# plugV17-Add-Large-Cap-to-support-RELAY-s.net
KiCad netlist of a schematic drawn in EAGLE
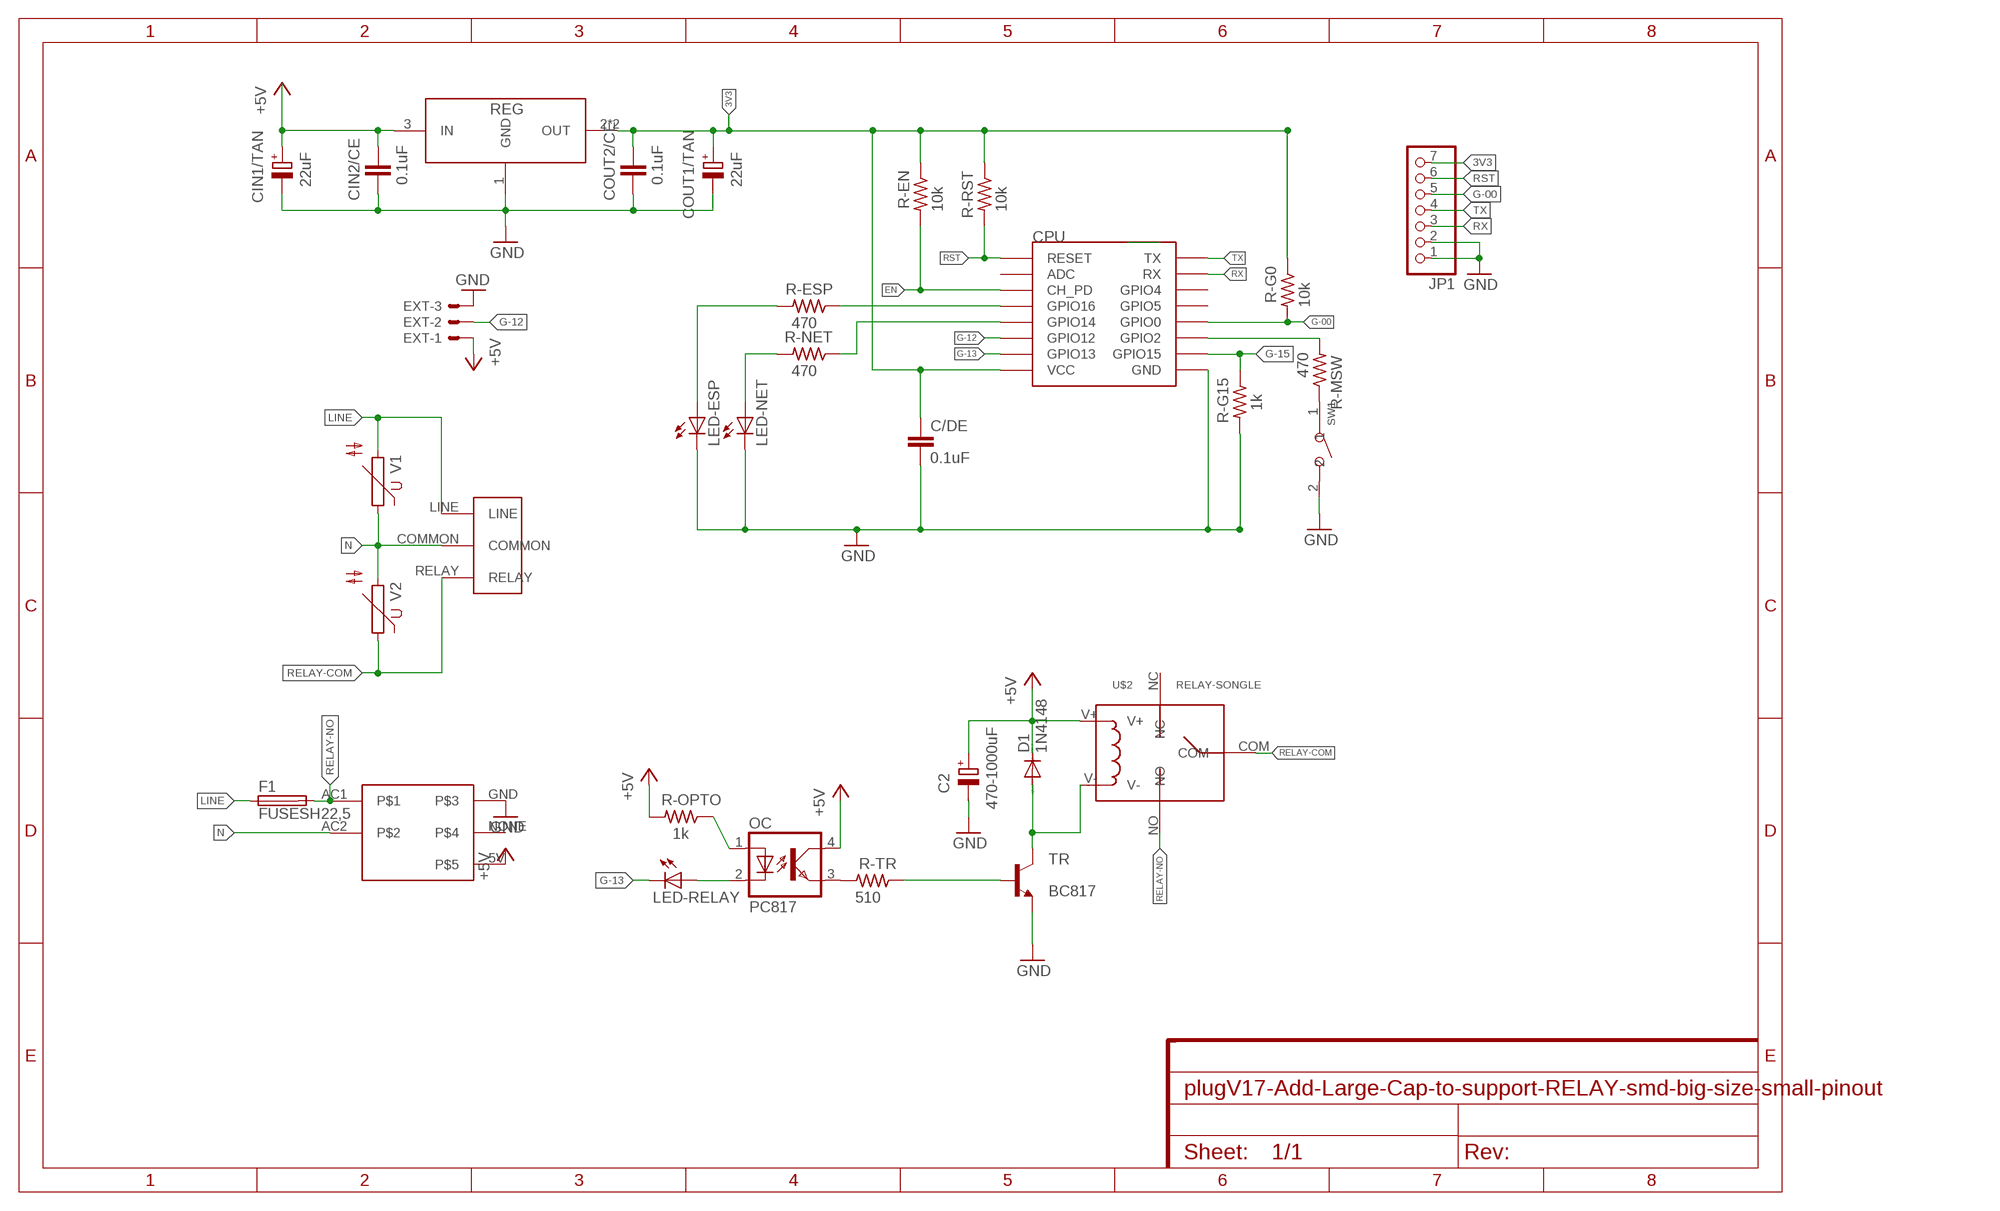
[diagram p0: schematic, sheet 1]

(export (version "E")
  (design (tool "Eeschema 10.0.6"))
  (components
    (comp (ref "C/DE")
      (value "0.1uF")
      (footprint "eagle-import:C0805")
      (libsource (lib "eagle-import") (part "C-EUC0805"))
    )
    (comp (ref "C2")
      (value "470-1000uF")
      (footprint "eagle-import:E3,5-8")
      (libsource (lib "eagle-import") (part "CPOL-EUE3.5-8"))
    )
    (comp (ref "CIN1/TAN")
      (value "22uF")
      (footprint "eagle-import:B_3528-21R")
      (libsource (lib "eagle-import") (part "CPOL-EUB/3528-21R"))
    )
    (comp (ref "CIN2/CE")
      (value "0.1uF")
      (footprint "eagle-import:C0805K")
      (libsource (lib "eagle-import") (part "C-EUC0805K"))
    )
    (comp (ref "COUT1/TAN")
      (value "22uF")
      (footprint "eagle-import:B_3528-21R")
      (libsource (lib "eagle-import") (part "CPOL-EUB/3528-21R"))
    )
    (comp (ref "COUT2/CE")
      (value "0.1uF")
      (footprint "eagle-import:C0805K")
      (libsource (lib "eagle-import") (part "C-EUC0805K"))
    )
    (comp (ref "CPU")
      (value "ESP12SMD")
      (footprint "eagle-import:ESP12-SMD")
      (libsource (lib "eagle-import") (part "ESP12SMD"))
    )
    (comp (ref "D1")
      (value "1N4148")
      (footprint "eagle-import:DO35-7")
      (libsource (lib "eagle-import") (part "1N4148DO35-7"))
    )
    (comp (ref "EXT")
      (value "53048-03")
      (footprint "eagle-import:53048-03")
      (fields (field (name "MF") "WALDOM/MOLEX") (field (name "MPN") "53048-0310"))
      (libsource (lib "eagle-import") (part "53?-03048"))
    )
    (comp (ref "F1")
      (value "FUSESH22,5")
      (footprint "eagle-import:SH22,5")
      (libsource (lib "eagle-import") (part "FUSESH22,5"))
    )
    (comp (ref "JP1")
      (value "PINHD-1X7")
      (footprint "eagle-import:1X07")
      (libsource (lib "eagle-import") (part "PINHD-1X7"))
    )
    (comp (ref "LED-ESP")
      (value "LEDCHIPLED_0805")
      (footprint "eagle-import:CHIPLED_0805")
      (libsource (lib "eagle-import") (part "LEDCHIPLED_0805"))
    )
    (comp (ref "LED-NET")
      (value "LEDCHIPLED_0805")
      (footprint "eagle-import:CHIPLED_0805")
      (libsource (lib "eagle-import") (part "LEDCHIPLED_0805"))
    )
    (comp (ref "LED-RELAY")
      (value "LEDCHIPLED_0805")
      (footprint "eagle-import:CHIPLED_0805")
      (libsource (lib "eagle-import") (part "LEDCHIPLED_0805"))
    )
    (comp (ref "OC")
      (value "PC817")
      (footprint "eagle-import:DIL04")
      (fields (field (name "MPN") "PC817X4J000F"))
      (libsource (lib "eagle-import") (part "PC817"))
    )
    (comp (ref "R-EN")
      (value "10k")
      (footprint "eagle-import:M0805")
      (libsource (lib "eagle-import") (part "R-US_M0805"))
    )
    (comp (ref "R-ESP")
      (value "470")
      (footprint "eagle-import:M0805")
      (libsource (lib "eagle-import") (part "R-US_M0805"))
    )
    (comp (ref "R-G0")
      (value "10k")
      (footprint "eagle-import:M0805")
      (libsource (lib "eagle-import") (part "R-US_M0805"))
    )
    (comp (ref "R-G15")
      (value "1k")
      (footprint "eagle-import:M0805")
      (libsource (lib "eagle-import") (part "R-US_M0805"))
    )
    (comp (ref "R-MSW")
      (value "470")
      (footprint "eagle-import:M0805")
      (libsource (lib "eagle-import") (part "R-US_M0805"))
    )
    (comp (ref "R-NET")
      (value "470")
      (footprint "eagle-import:M0805")
      (libsource (lib "eagle-import") (part "R-US_M0805"))
    )
    (comp (ref "R-OPTO")
      (value "1k")
      (footprint "eagle-import:M0805")
      (libsource (lib "eagle-import") (part "R-US_M0805"))
    )
    (comp (ref "R-RST")
      (value "10k")
      (footprint "eagle-import:M0805")
      (libsource (lib "eagle-import") (part "R-US_M0805"))
    )
    (comp (ref "R-TR")
      (value "510")
      (footprint "eagle-import:M0805")
      (libsource (lib "eagle-import") (part "R-US_M0805"))
    )
    (comp (ref "REG")
      (value "AMS1117-3.3")
      (footprint "eagle-import:SOT-223")
      (libsource (lib "eagle-import") (part "AMS1117-3.3"))
    )
    (comp (ref "SW1")
      (value "DIP-BUTTON(2P-6.0X3.0X4.3MM)-TS-1101F")
      (footprint "eagle-import:SW2-5.0-6.0X3.0X4.3MM")
      (libsource (lib "eagle-import") (part "DIP-BUTTON(2P-6.0X3.0X4.3MM)-TS-1101F"))
    )
    (comp (ref "TR")
      (value "BC817")
      (footprint "eagle-import:SOT23-BEC")
      (libsource (lib "eagle-import") (part "BC817SMD-16"))
    )
    (comp (ref "U$1")
      (value "POWER-RELAY-FOOTPRINT")
      (footprint "eagle-import:POWER-RELAY-FOOTPRINT")
      (libsource (lib "eagle-import") (part "POWER-RELAY-FOOTPRINT"))
    )
    (comp (ref "U$2")
      (value "RELAY-SONGLE")
      (footprint "eagle-import:RELAY-SONGLE")
      (libsource (lib "eagle-import") (part "RELAY-SONGLE"))
    )
    (comp (ref "U$4")
      (value "POWERSUPPLY-5V-700MA")
      (footprint "eagle-import:POWERSUPPLY-5V-700MA")
      (libsource (lib "eagle-import") (part "POWERSUPPLY-5V-700MA"))
    )
    (comp (ref "V1")
      (value "S14K11")
      (footprint "eagle-import:S14K11")
      (libsource (lib "eagle-import") (part "S14K11"))
    )
    (comp (ref "V2")
      (value "S14K11")
      (footprint "eagle-import:S14K11")
      (libsource (lib "eagle-import") (part "S14K11"))
    )
  )
  (nets
    (net (code "1") (name "+5V") (class "Default")
      (node (ref "C2") (pin "+") (pinfunction "+_+") (pintype "passive"))
      (node (ref "CIN1/TAN") (pin "+") (pinfunction "+_+") (pintype "passive"))
      (node (ref "CIN2/CE") (pin "1") (pinfunction "1_1") (pintype "passive"))
      (node (ref "D1") (pin "C") (pinfunction "C_C") (pintype "passive"))
      (node (ref "EXT") (pin "1") (pinfunction "S_1") (pintype "passive"))
      (node (ref "OC") (pin "4") (pinfunction "COL_4") (pintype "passive"))
      (node (ref "R-OPTO") (pin "2") (pinfunction "2_2") (pintype "passive"))
      (node (ref "REG") (pin "3") (pinfunction "IN_3") (pintype "input"))
      (node (ref "U$2") (pin "V+") (pinfunction "V+_V+") (pintype "bidirectional"))
      (node (ref "U$4") (pin "5V") (pinfunction "P$5_5V") (pintype "bidirectional"))
    )
    (net (code "2") (name "3V3") (class "Default")
      (node (ref "C/DE") (pin "1") (pinfunction "1_1") (pintype "passive"))
      (node (ref "COUT1/TAN") (pin "+") (pinfunction "+_+") (pintype "passive"))
      (node (ref "COUT2/CE") (pin "1") (pinfunction "1_1") (pintype "passive"))
      (node (ref "CPU") (pin "VCC") (pinfunction "VCC_VCC") (pintype "bidirectional"))
      (node (ref "JP1") (pin "7") (pinfunction "7_7") (pintype "passive"))
      (node (ref "R-EN") (pin "1") (pinfunction "1_1") (pintype "passive"))
      (node (ref "R-G0") (pin "1") (pinfunction "1_1") (pintype "passive"))
      (node (ref "R-RST") (pin "1") (pinfunction "1_1") (pintype "passive"))
      (node (ref "REG") (pin "2") (pinfunction "OUT_2") (pintype "output"))
      (node (ref "REG") (pin "4") (pinfunction "OUT_4") (pintype "output"))
    )
    (net (code "3") (name "EN") (class "Default")
      (node (ref "CPU") (pin "CH_PD") (pinfunction "CH_PD_CH_PD") (pintype "bidirectional"))
      (node (ref "R-EN") (pin "2") (pinfunction "2_2") (pintype "passive"))
    )
    (net (code "4") (name "G-00") (class "Default")
      (node (ref "CPU") (pin "GPIO0") (pinfunction "GPIO0_GPIO0") (pintype "bidirectional"))
      (node (ref "JP1") (pin "5") (pinfunction "5_5") (pintype "passive"))
      (node (ref "R-G0") (pin "2") (pinfunction "2_2") (pintype "passive"))
    )
    (net (code "5") (name "G-12") (class "Default")
      (node (ref "CPU") (pin "GPIO12") (pinfunction "GPIO12_GPIO12") (pintype "bidirectional"))
      (node (ref "EXT") (pin "2") (pinfunction "S_2") (pintype "passive"))
    )
    (net (code "6") (name "G-13") (class "Default")
      (node (ref "CPU") (pin "GPIO13") (pinfunction "GPIO13_GPIO13") (pintype "bidirectional"))
      (node (ref "LED-RELAY") (pin "C") (pinfunction "C_C") (pintype "passive"))
    )
    (net (code "7") (name "G-15") (class "Default")
      (node (ref "CPU") (pin "GPIO15") (pinfunction "GPIO15_GPIO15") (pintype "bidirectional"))
      (node (ref "R-G15") (pin "1") (pinfunction "1_1") (pintype "passive"))
    )
    (net (code "8") (name "GND") (class "Default")
      (node (ref "C/DE") (pin "2") (pinfunction "2_2") (pintype "passive"))
      (node (ref "C2") (pin "-") (pinfunction "-_-") (pintype "passive"))
      (node (ref "CIN1/TAN") (pin "-") (pinfunction "-_-") (pintype "passive"))
      (node (ref "CIN2/CE") (pin "2") (pinfunction "2_2") (pintype "passive"))
      (node (ref "COUT1/TAN") (pin "-") (pinfunction "-_-") (pintype "passive"))
      (node (ref "COUT2/CE") (pin "2") (pinfunction "2_2") (pintype "passive"))
      (node (ref "CPU") (pin "GND") (pinfunction "GND_GND") (pintype "bidirectional"))
      (node (ref "EXT") (pin "3") (pinfunction "S_3") (pintype "passive"))
      (node (ref "JP1") (pin "1") (pinfunction "1_1") (pintype "passive"))
      (node (ref "JP1") (pin "2") (pinfunction "2_2") (pintype "passive"))
      (node (ref "LED-ESP") (pin "C") (pinfunction "C_C") (pintype "passive"))
      (node (ref "LED-NET") (pin "C") (pinfunction "C_C") (pintype "passive"))
      (node (ref "R-G15") (pin "2") (pinfunction "2_2") (pintype "passive"))
      (node (ref "REG") (pin "1") (pinfunction "GND_1") (pintype "passive"))
      (node (ref "SW1") (pin "2") (pinfunction "2_2") (pintype "bidirectional"))
      (node (ref "TR") (pin "E") (pinfunction "E_E") (pintype "passive"))
      (node (ref "U$4") (pin "GND") (pinfunction "P$3_GND") (pintype "bidirectional"))
    )
    (net (code "9") (name "LINE") (class "Default")
      (node (ref "F1") (pin "1") (pinfunction "1_1") (pintype "passive"))
      (node (ref "U$1") (pin "LINE") (pinfunction "LINE_LINE") (pintype "bidirectional"))
      (node (ref "V1") (pin "2") (pinfunction "2_2") (pintype "passive"))
    )
    (net (code "10") (name "N") (class "Default")
      (node (ref "U$1") (pin "COMMON") (pinfunction "COMMON_COMMON") (pintype "bidirectional"))
      (node (ref "U$4") (pin "AC2") (pinfunction "P$2_AC2") (pintype "bidirectional"))
      (node (ref "V1") (pin "1") (pinfunction "1_1") (pintype "passive"))
      (node (ref "V2") (pin "2") (pinfunction "2_2") (pintype "passive"))
    )
    (net (code "11") (name "Net-(CPU-PadGPIO2)") (class "Default")
      (node (ref "CPU") (pin "GPIO2") (pinfunction "GPIO2_GPIO2") (pintype "bidirectional"))
      (node (ref "R-MSW") (pin "2") (pinfunction "2_2") (pintype "passive"))
    )
    (net (code "12") (name "Net-(CPU-PadGPIO14)") (class "Default")
      (node (ref "CPU") (pin "GPIO14") (pinfunction "GPIO14_GPIO14") (pintype "bidirectional"))
      (node (ref "R-NET") (pin "1") (pinfunction "1_1") (pintype "passive"))
    )
    (net (code "13") (name "Net-(CPU-PadGPIO16)") (class "Default")
      (node (ref "CPU") (pin "GPIO16") (pinfunction "GPIO16_GPIO16") (pintype "bidirectional"))
      (node (ref "R-ESP") (pin "1") (pinfunction "1_1") (pintype "passive"))
    )
    (net (code "14") (name "Net-(D1-PadA)") (class "Default")
      (node (ref "D1") (pin "A") (pinfunction "A_A") (pintype "passive"))
      (node (ref "TR") (pin "C") (pinfunction "C_C") (pintype "passive"))
      (node (ref "U$2") (pin "V-") (pinfunction "V-_V-") (pintype "bidirectional"))
    )
    (net (code "15") (name "Net-(LED-ESP-PadA)") (class "Default")
      (node (ref "LED-ESP") (pin "A") (pinfunction "A_A") (pintype "passive"))
      (node (ref "R-ESP") (pin "2") (pinfunction "2_2") (pintype "passive"))
    )
    (net (code "16") (name "Net-(LED-NET-PadA)") (class "Default")
      (node (ref "LED-NET") (pin "A") (pinfunction "A_A") (pintype "passive"))
      (node (ref "R-NET") (pin "2") (pinfunction "2_2") (pintype "passive"))
    )
    (net (code "17") (name "Net-(OC-A)") (class "Default")
      (node (ref "OC") (pin "1") (pinfunction "A_1") (pintype "passive"))
      (node (ref "R-OPTO") (pin "1") (pinfunction "1_1") (pintype "passive"))
    )
    (net (code "18") (name "Net-(OC-C)") (class "Default")
      (node (ref "LED-RELAY") (pin "A") (pinfunction "A_A") (pintype "passive"))
      (node (ref "OC") (pin "2") (pinfunction "C_2") (pintype "passive"))
    )
    (net (code "19") (name "Net-(OC-EMIT)") (class "Default")
      (node (ref "OC") (pin "3") (pinfunction "EMIT_3") (pintype "passive"))
      (node (ref "R-TR") (pin "2") (pinfunction "2_2") (pintype "passive"))
    )
    (net (code "20") (name "Net-(R-MSW-Pad1)") (class "Default")
      (node (ref "R-MSW") (pin "1") (pinfunction "1_1") (pintype "passive"))
      (node (ref "SW1") (pin "1") (pinfunction "1_1") (pintype "bidirectional"))
    )
    (net (code "21") (name "Net-(R-TR-Pad1)") (class "Default")
      (node (ref "R-TR") (pin "1") (pinfunction "1_1") (pintype "passive"))
      (node (ref "TR") (pin "B") (pinfunction "B_B") (pintype "passive"))
    )
    (net (code "22") (name "RELAY-COM") (class "Default")
      (node (ref "U$1") (pin "RELAY") (pinfunction "RELAY_RELAY") (pintype "bidirectional"))
      (node (ref "U$2") (pin "COM") (pinfunction "COM_COM") (pintype "bidirectional"))
      (node (ref "V2") (pin "1") (pinfunction "1_1") (pintype "passive"))
    )
    (net (code "23") (name "RELAY-NO") (class "Default")
      (node (ref "F1") (pin "2") (pinfunction "2_2") (pintype "passive"))
      (node (ref "U$2") (pin "NO") (pinfunction "NO_NO") (pintype "bidirectional"))
      (node (ref "U$4") (pin "AC1") (pinfunction "P$1_AC1") (pintype "bidirectional"))
    )
    (net (code "24") (name "RST") (class "Default")
      (node (ref "CPU") (pin "RESET") (pinfunction "RESET_RESET") (pintype "bidirectional"))
      (node (ref "JP1") (pin "6") (pinfunction "6_6") (pintype "passive"))
      (node (ref "R-RST") (pin "2") (pinfunction "2_2") (pintype "passive"))
    )
    (net (code "25") (name "RX") (class "Default")
      (node (ref "CPU") (pin "RXD0") (pinfunction "RX_RXD0") (pintype "bidirectional"))
      (node (ref "JP1") (pin "3") (pinfunction "3_3") (pintype "passive"))
    )
    (net (code "26") (name "TX") (class "Default")
      (node (ref "CPU") (pin "TXD0") (pinfunction "TX_TXD0") (pintype "bidirectional"))
      (node (ref "JP1") (pin "4") (pinfunction "4_4") (pintype "passive"))
    )
    (net (code "27") (name "unconnected-(CPU-PadADC)") (class "Default")
      (node (ref "CPU") (pin "ADC") (pinfunction "ADC_ADC") (pintype "bidirectional"))
    )
    (net (code "28") (name "unconnected-(CPU-PadGPIO4)") (class "Default")
      (node (ref "CPU") (pin "GPIO4") (pinfunction "GPIO4_GPIO4") (pintype "bidirectional"))
    )
    (net (code "29") (name "unconnected-(CPU-PadGPIO5)") (class "Default")
      (node (ref "CPU") (pin "GPIO5") (pinfunction "GPIO5_GPIO5") (pintype "bidirectional"))
    )
    (net (code "30") (name "unconnected-(U$2-PadNC)") (class "Default")
      (node (ref "U$2") (pin "NC") (pinfunction "NC_NC") (pintype "bidirectional"))
    )
    (net (code "31") (name "unconnected-(U$4-P$4-PadNONE)") (class "Default")
      (node (ref "U$4") (pin "NONE") (pinfunction "P$4_NONE") (pintype "bidirectional"))
    )
  )
)
